# KC_BaseBoard4CompareTest-V0_21.net
KiCad netlist of a schematic drawn in Altium Designer
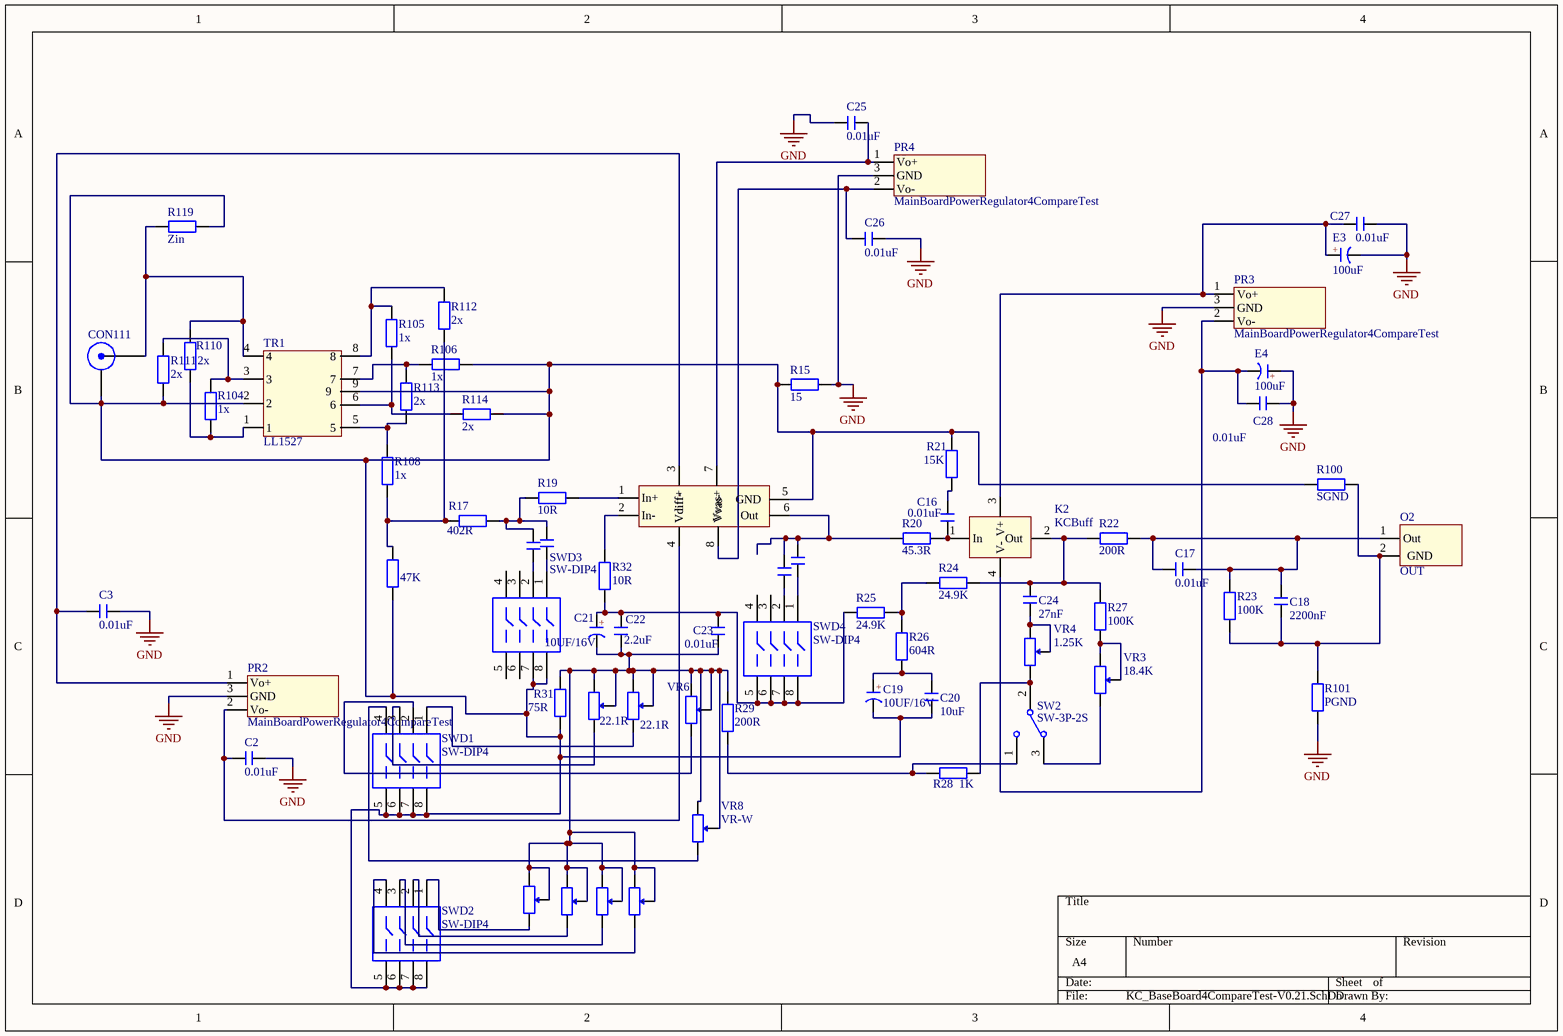
[diagram p0: KC_BaseBoard4CompareTest-V0.21.SchDoc]

(export (version "E")
  (design (tool "Eeschema 10.0.6"))
  (components
    (comp (ref "C2")
      (value "0.01uF")
      (footprint "CBB 6.3*6.3*5")
      (description "CBB电容")
      (fields (field (name "版权归属") "源创客"))
      (libsource (lib "电阻-电容-电感") (part "C-CBB"))
    )
    (comp (ref "C3")
      (value "0.01uF")
      (footprint "CBB 6.3*6.3*5")
      (description "CBB电容")
      (fields (field (name "版权归属") "源创客"))
      (libsource (lib "电阻-电容-电感") (part "C-CBB"))
    )
    (comp (ref "C16")
      (value "0.01uF")
      (footprint "CBB 6.3*6.3*5")
      (description "CBB电容")
      (fields (field (name "版权归属") "源创客"))
      (libsource (lib "电阻-电容-电感") (part "C-CBB"))
    )
    (comp (ref "C17")
      (value "0.01uF")
      (footprint "CBB 6.3*6.3*5")
      (description "CBB电容")
      (fields (field (name "版权归属") "源创客"))
      (libsource (lib "电阻-电容-电感") (part "C-CBB"))
    )
    (comp (ref "C18")
      (value "2200nF")
      (footprint "CBB 6.3*6.3*5")
      (description "CBB电容")
      (fields (field (name "版权归属") "源创客"))
      (libsource (lib "电阻-电容-电感") (part "C-CBB"))
    )
    (comp (ref "C19")
      (value "10UF/16V")
      (footprint "CAP 5.0*10*12.5")
      (description "直插电解电容")
      (fields (field (name "版权归属") "源创客"))
      (libsource (lib "电阻-电容-电感") (part "C-CAP"))
    )
    (comp (ref "C20")
      (value "10uF")
      (footprint "CBB 6.3*6.3*5")
      (description "CBB电容")
      (fields (field (name "版权归属") "源创客"))
      (libsource (lib "电阻-电容-电感") (part "C-CBB"))
    )
    (comp (ref "C21")
      (value "10UF/16V")
      (footprint "CAP 5.0*10*12.5")
      (description "直插电解电容")
      (fields (field (name "版权归属") "源创客"))
      (libsource (lib "电阻-电容-电感") (part "C-CAP"))
    )
    (comp (ref "C22")
      (value "2.2uF")
      (footprint "CBB 6.3*6.3*5")
      (description "CBB电容")
      (fields (field (name "版权归属") "源创客"))
      (libsource (lib "电阻-电容-电感") (part "C-CBB"))
    )
    (comp (ref "C23")
      (value "0.01uF")
      (footprint "CBB 6.3*6.3*5")
      (description "CBB电容")
      (fields (field (name "版权归属") "源创客"))
      (libsource (lib "电阻-电容-电感") (part "C-CBB"))
    )
    (comp (ref "C24")
      (value "27nF")
      (footprint "CBB 6.3*6.3*5")
      (description "CBB电容")
      (fields (field (name "版权归属") "源创客"))
      (libsource (lib "电阻-电容-电感") (part "C-CBB"))
    )
    (comp (ref "C25")
      (value "0.01uF")
      (footprint "CBB 6.3*6.3*5")
      (description "CBB电容")
      (fields (field (name "版权归属") "源创客"))
      (libsource (lib "电阻-电容-电感") (part "C-CBB"))
    )
    (comp (ref "C26")
      (value "0.01uF")
      (footprint "CBB 6.3*6.3*5")
      (description "CBB电容")
      (fields (field (name "版权归属") "源创客"))
      (libsource (lib "电阻-电容-电感") (part "C-CBB"))
    )
    (comp (ref "C27")
      (value "0.01uF")
      (footprint "CBB 6.3*6.3*5")
      (description "CBB电容")
      (fields (field (name "版权归属") "源创客"))
      (libsource (lib "电阻-电容-电感") (part "C-CBB"))
    )
    (comp (ref "C28")
      (value "0.01uF")
      (footprint "CBB 6.3*6.3*5")
      (description "CBB电容")
      (fields (field (name "版权归属") "源创客"))
      (libsource (lib "电阻-电容-电感") (part "C-CBB"))
    )
    (comp (ref "C302")
      (value "100pF")
      (footprint "CBB 6.3*6.3*5")
      (description "CBB电容")
      (fields (field (name "版权归属") "源创客"))
      (libsource (lib "电阻-电容-电感") (part "C-CBB"))
    )
    (comp (ref "C303")
      (value "20pF")
      (footprint "CBB 6.3*6.3*5")
      (description "CBB电容")
      (fields (field (name "版权归属") "源创客"))
      (libsource (lib "电阻-电容-电感") (part "C-CBB"))
    )
    (comp (ref "C402")
      (value "100pF")
      (footprint "CBB 6.3*6.3*5")
      (description "CBB电容")
      (fields (field (name "版权归属") "源创客"))
      (libsource (lib "电阻-电容-电感") (part "C-CBB"))
    )
    (comp (ref "C403")
      (value "20pF")
      (footprint "CBB 6.3*6.3*5")
      (description "CBB电容")
      (fields (field (name "版权归属") "源创客"))
      (libsource (lib "电阻-电容-电感") (part "C-CBB"))
    )
    (comp (ref "CON111")
      (value "RCA")
      (footprint "RCA-RJ255")
      (description "RCA Connector")
      (fields (field (name "PUBLISHER") "Altium Limited"))
      (libsource (lib "Connectors") (part "RCA"))
    )
    (comp (ref "E3")
      (value "100uF")
      (footprint "CAP 5.0*6.5*12.5")
      (description "直插电解电容")
      (fields (field (name "版权归属") "源创客"))
      (libsource (lib "") (part "C-CAP_1"))
    )
    (comp (ref "E4")
      (value "100uF")
      (footprint "CAP 5.0*6.5*12.5")
      (description "直插电解电容")
      (fields (field (name "版权归属") "源创客"))
      (libsource (lib "") (part "C-CAP_1"))
    )
    (comp (ref "K2")
      (value "KCBuff")
      (footprint "KCBuff_M4")
      (description "King Cello Buffer Stage")
      (libsource (lib "KC_amp") (part "KCBuff"))
    )
    (comp (ref "KC2")
      (value "KCInputVas_V0.2")
      (footprint "KCIn_VAS_M4_V0.2")
      (description "King Cello Input Stage and VAS")
      (libsource (lib "KC_amp") (part "KCInputVas_V0.2"))
    )
    (comp (ref "O2")
      (value "OUT")
      (footprint "Signal_Terminal")
      (description "Signal Out")
      (libsource (lib "KC_amp") (part "Signal_Out"))
    )
    (comp (ref "PR2")
      (value "MainBoardPowerRegulator4CompareTest")
      (footprint "KC_MBPowerReg4Compare")
      (description "King Cello Compare Test Power")
      (libsource (lib "KC_amp") (part "MainBoardPowerRegulator4CompareTest"))
    )
    (comp (ref "PR3")
      (value "MainBoardPowerRegulator4CompareTest")
      (footprint "KC_MBPowerReg4Compare")
      (description "King Cello Compare Test Power")
      (libsource (lib "KC_amp") (part "MainBoardPowerRegulator4CompareTest"))
    )
    (comp (ref "PR4")
      (value "MainBoardPowerRegulator4CompareTest")
      (footprint "KC_MBPowerReg4Compare")
      (description "King Cello Compare Test Power")
      (libsource (lib "KC_amp") (part "MainBoardPowerRegulator4CompareTest"))
    )
    (comp (ref "R15")
      (value "15")
      (footprint "RS 1/4W")
      (description "直插色环电阻")
      (fields (field (name "版权归属") "源创客"))
      (libsource (lib "电阻-电容-电感") (part "R-CRR"))
    )
    (comp (ref "R17")
      (value "402R")
      (footprint "RS 1/4W")
      (description "直插色环电阻")
      (fields (field (name "版权归属") "源创客"))
      (libsource (lib "电阻-电容-电感") (part "R-CRR"))
    )
    (comp (ref "R19")
      (value "10R")
      (footprint "RS 1/4W")
      (description "直插色环电阻")
      (fields (field (name "版权归属") "源创客"))
      (libsource (lib "电阻-电容-电感") (part "R-CRR"))
    )
    (comp (ref "R20")
      (value "45.3R")
      (footprint "RS 1/4W")
      (description "直插色环电阻")
      (fields (field (name "版权归属") "源创客"))
      (libsource (lib "电阻-电容-电感") (part "R-CRR"))
    )
    (comp (ref "R21")
      (value "15K")
      (footprint "RS 1/4W")
      (description "直插色环电阻")
      (fields (field (name "版权归属") "源创客"))
      (libsource (lib "电阻-电容-电感") (part "R-CRR"))
    )
    (comp (ref "R22")
      (value "200R")
      (footprint "RS 1/4W")
      (description "直插色环电阻")
      (fields (field (name "版权归属") "源创客"))
      (libsource (lib "电阻-电容-电感") (part "R-CRR"))
    )
    (comp (ref "R23")
      (value "100K")
      (footprint "RS 1/4W")
      (description "直插色环电阻")
      (fields (field (name "版权归属") "源创客"))
      (libsource (lib "电阻-电容-电感") (part "R-CRR"))
    )
    (comp (ref "R24")
      (value "24.9K")
      (footprint "RS 1/4W")
      (description "直插色环电阻")
      (fields (field (name "版权归属") "源创客"))
      (libsource (lib "电阻-电容-电感") (part "R-CRR"))
    )
    (comp (ref "R25")
      (value "24.9K")
      (footprint "RS 1/4W")
      (description "直插色环电阻")
      (fields (field (name "版权归属") "源创客"))
      (libsource (lib "电阻-电容-电感") (part "R-CRR"))
    )
    (comp (ref "R26")
      (value "604R")
      (footprint "RS 1/4W")
      (description "直插色环电阻")
      (fields (field (name "版权归属") "源创客"))
      (libsource (lib "电阻-电容-电感") (part "R-CRR"))
    )
    (comp (ref "R27")
      (value "100K")
      (footprint "RS 1/4W")
      (description "直插色环电阻")
      (fields (field (name "版权归属") "源创客"))
      (libsource (lib "电阻-电容-电感") (part "R-CRR"))
    )
    (comp (ref "R28")
      (value "1K")
      (footprint "RS 1/4W")
      (description "直插色环电阻")
      (fields (field (name "版权归属") "源创客"))
      (libsource (lib "电阻-电容-电感") (part "R-CRR"))
    )
    (comp (ref "R29")
      (value "200R")
      (footprint "RS 1/4W")
      (description "直插色环电阻")
      (fields (field (name "版权归属") "源创客"))
      (libsource (lib "电阻-电容-电感") (part "R-CRR"))
    )
    (comp (ref "R31")
      (value "75R")
      (footprint "RS 1/4W")
      (description "直插色环电阻")
      (fields (field (name "版权归属") "源创客"))
      (libsource (lib "电阻-电容-电感") (part "R-CRR"))
    )
    (comp (ref "R32")
      (value "10R")
      (footprint "RS 1/4W")
      (description "直插色环电阻")
      (fields (field (name "版权归属") "源创客"))
      (libsource (lib "电阻-电容-电感") (part "R-CRR"))
    )
    (comp (ref "R100")
      (value "SGND")
      (footprint "RS 1/4W")
      (description "直插色环电阻")
      (fields (field (name "版权归属") "源创客"))
      (libsource (lib "电阻-电容-电感") (part "R-CRR"))
    )
    (comp (ref "R101")
      (value "PGND")
      (footprint "RS 1/4W")
      (description "直插色环电阻")
      (fields (field (name "版权归属") "源创客"))
      (libsource (lib "电阻-电容-电感") (part "R-CRR"))
    )
    (comp (ref "R104")
      (value "1x")
      (footprint "RS 1/4W")
      (description "直插色环电阻")
      (fields (field (name "版权归属") "源创客"))
      (libsource (lib "电阻-电容-电感") (part "R-CRR"))
    )
    (comp (ref "R105")
      (value "1x")
      (footprint "RS 1/4W")
      (description "直插色环电阻")
      (fields (field (name "版权归属") "源创客"))
      (libsource (lib "电阻-电容-电感") (part "R-CRR"))
    )
    (comp (ref "R106")
      (value "1x")
      (footprint "RS 1/4W")
      (description "直插色环电阻")
      (fields (field (name "版权归属") "源创客"))
      (libsource (lib "电阻-电容-电感") (part "R-CRR"))
    )
    (comp (ref "R108")
      (value "1x")
      (footprint "RS 1/4W")
      (description "直插色环电阻")
      (fields (field (name "版权归属") "源创客"))
      (libsource (lib "电阻-电容-电感") (part "R-CRR"))
    )
    (comp (ref "R110")
      (value "2x")
      (footprint "RS 1/4W")
      (description "直插色环电阻")
      (fields (field (name "版权归属") "源创客"))
      (libsource (lib "电阻-电容-电感") (part "R-CRR"))
    )
    (comp (ref "R111")
      (value "2x")
      (footprint "RS 1/4W")
      (description "直插色环电阻")
      (fields (field (name "版权归属") "源创客"))
      (libsource (lib "电阻-电容-电感") (part "R-CRR"))
    )
    (comp (ref "R112")
      (value "2x")
      (footprint "RS 1/4W")
      (description "直插色环电阻")
      (fields (field (name "版权归属") "源创客"))
      (libsource (lib "电阻-电容-电感") (part "R-CRR"))
    )
    (comp (ref "R113")
      (value "2x")
      (footprint "RS 1/4W")
      (description "直插色环电阻")
      (fields (field (name "版权归属") "源创客"))
      (libsource (lib "电阻-电容-电感") (part "R-CRR"))
    )
    (comp (ref "R114")
      (value "2x")
      (footprint "RS 1/4W")
      (description "直插色环电阻")
      (fields (field (name "版权归属") "源创客"))
      (libsource (lib "电阻-电容-电感") (part "R-CRR"))
    )
    (comp (ref "R119")
      (value "Zin")
      (footprint "RS 1/4W")
      (description "直插色环电阻")
      (fields (field (name "版权归属") "源创客"))
      (libsource (lib "电阻-电容-电感") (part "R-CRR"))
    )
    (comp (ref "R183")
      (value "47K")
      (footprint "RS 1/4W")
      (description "直插色环电阻")
      (fields (field (name "版权归属") "源创客"))
      (libsource (lib "电阻-电容-电感") (part "R-CRR"))
    )
    (comp (ref "SW2")
      (value "SW-3P-2S")
      (footprint "SS-12D06")
      (description "3 Pin 2 Switch")
      (libsource (lib "Connectors") (part "SW-3P-2S"))
    )
    (comp (ref "SWD1")
      (value "SW-DIP4")
      (footprint "DIP-8")
      (description "DIP Switch")
      (fields (field (name "PUBLISHER") "Altium Limited"))
      (libsource (lib "Miscellaneous Devices") (part "SW-DIP4"))
    )
    (comp (ref "SWD2")
      (value "SW-DIP4")
      (footprint "DIP-8")
      (description "DIP Switch")
      (fields (field (name "PUBLISHER") "Altium Limited"))
      (libsource (lib "Miscellaneous Devices") (part "SW-DIP4"))
    )
    (comp (ref "SWD3")
      (value "SW-DIP4")
      (footprint "DIP-8")
      (description "DIP Switch")
      (fields (field (name "PUBLISHER") "Altium Limited"))
      (libsource (lib "Miscellaneous Devices") (part "SW-DIP4"))
    )
    (comp (ref "SWD4")
      (value "SW-DIP4")
      (footprint "DIP-8")
      (description "DIP Switch")
      (fields (field (name "PUBLISHER") "Altium Limited"))
      (libsource (lib "Miscellaneous Devices") (part "SW-DIP4"))
    )
    (comp (ref "TR1")
      (value "LL1527")
      (footprint "LL1527")
      (description "Lundahl LL1527")
      (libsource (lib "KC_amp") (part "LL1527"))
    )
    (comp (ref "VR3")
      (value "18.4K")
      (footprint "RS 1/2W-VR")
      (description "直插可调电阻-顶调")
      (libsource (lib "电阻-电容-电感") (part "VR-W"))
    )
    (comp (ref "VR4")
      (value "1.25K")
      (footprint "RS 1/2W-VR")
      (description "直插可调电阻-顶调")
      (libsource (lib "电阻-电容-电感") (part "VR-W"))
    )
    (comp (ref "VR5")
      (value "22.1R")
      (footprint "RS 1/2W-VR")
      (description "直插可调电阻-顶调")
      (libsource (lib "电阻-电容-电感") (part "VR-W"))
    )
    (comp (ref "VR6")
      (value "22.1R")
      (footprint "RS 1/2W-VR")
      (description "直插可调电阻-顶调")
      (libsource (lib "电阻-电容-电感") (part "VR-W"))
    )
    (comp (ref "VR7")
      (value "VR-W")
      (footprint "RS 1/2W-VR")
      (description "直插可调电阻-顶调")
      (libsource (lib "电阻-电容-电感") (part "VR-W"))
    )
    (comp (ref "VR8")
      (value "VR-W")
      (footprint "RS 1/2W-VR")
      (description "直插可调电阻-顶调")
      (libsource (lib "电阻-电容-电感") (part "VR-W"))
    )
    (comp (ref "VR9")
      (value "VR-W")
      (footprint "RS 1/2W-VR")
      (description "直插可调电阻-顶调")
      (libsource (lib "电阻-电容-电感") (part "VR-W"))
    )
    (comp (ref "VR10")
      (value "VR-W")
      (footprint "RS 1/2W-VR")
      (description "直插可调电阻-顶调")
      (libsource (lib "电阻-电容-电感") (part "VR-W"))
    )
    (comp (ref "VR11")
      (value "VR-W")
      (footprint "RS 1/2W-VR")
      (description "直插可调电阻-顶调")
      (libsource (lib "电阻-电容-电感") (part "VR-W"))
    )
    (comp (ref "VR12")
      (value "VR-W")
      (footprint "RS 1/2W-VR")
      (description "直插可调电阻-顶调")
      (libsource (lib "电阻-电容-电感") (part "VR-W"))
    )
  )
  (nets
    (net (code "1") (name "GND") (class "Default")
      (node (ref "C2") (pin "2") (pinfunction "2_2") (pintype "passive"))
      (node (ref "C25") (pin "1") (pinfunction "1_1") (pintype "passive"))
      (node (ref "C26") (pin "2") (pinfunction "2_2") (pintype "passive"))
      (node (ref "C27") (pin "2") (pinfunction "2_2") (pintype "passive"))
      (node (ref "C28") (pin "2") (pinfunction "2_2") (pintype "passive"))
      (node (ref "C3") (pin "2") (pinfunction "2_2") (pintype "passive"))
      (node (ref "E3") (pin "2") (pinfunction "K_2") (pintype "passive"))
      (node (ref "E4") (pin "1") (pinfunction "A_1") (pintype "passive"))
      (node (ref "PR2") (pin "3") (pinfunction "GND_3") (pintype "passive"))
      (node (ref "PR3") (pin "3") (pinfunction "GND_3") (pintype "passive"))
      (node (ref "PR4") (pin "3") (pinfunction "GND_3") (pintype "passive"))
      (node (ref "R101") (pin "1") (pinfunction "1_1") (pintype "passive"))
      (node (ref "R15") (pin "2") (pinfunction "2_2") (pintype "passive"))
    )
    (net (code "2") (name "Net-(C16-Pad2)") (class "Default")
      (node (ref "C16") (pin "2") (pinfunction "2_2") (pintype "passive"))
      (node (ref "R21") (pin "1") (pinfunction "1_1") (pintype "passive"))
    )
    (net (code "3") (name "Net-(C19-A)") (class "Default")
      (node (ref "C19") (pin "1") (pinfunction "A_1") (pintype "passive"))
      (node (ref "C20") (pin "1") (pinfunction "1_1") (pintype "passive"))
      (node (ref "R26") (pin "1") (pinfunction "1_1") (pintype "passive"))
    )
    (net (code "4") (name "Net-(C19-K)") (class "Default")
      (node (ref "C19") (pin "2") (pinfunction "K_2") (pintype "passive"))
      (node (ref "C20") (pin "2") (pinfunction "2_2") (pintype "passive"))
      (node (ref "CON111") (pin "2") (pinfunction "Y_2") (pintype "passive"))
      (node (ref "KC2") (pin "5") (pinfunction "GND_5") (pintype "passive"))
      (node (ref "R100") (pin "1") (pinfunction "1_1") (pintype "passive"))
      (node (ref "R106") (pin "2") (pinfunction "2_2") (pintype "passive"))
      (node (ref "R111") (pin "1") (pinfunction "1_1") (pintype "passive"))
      (node (ref "R114") (pin "2") (pinfunction "2_2") (pintype "passive"))
      (node (ref "R119") (pin "2") (pinfunction "2_2") (pintype "passive"))
      (node (ref "R15") (pin "1") (pinfunction "1_1") (pintype "passive"))
      (node (ref "R183") (pin "1") (pinfunction "1_1") (pintype "passive"))
      (node (ref "R21") (pin "2") (pinfunction "2_2") (pintype "passive"))
      (node (ref "R31") (pin "1") (pinfunction "1_1") (pintype "passive"))
      (node (ref "SWD1") (pin "5") (pinfunction "5_5") (pintype "passive"))
      (node (ref "SWD1") (pin "6") (pinfunction "6_6") (pintype "passive"))
      (node (ref "SWD1") (pin "7") (pinfunction "7_7") (pintype "passive"))
      (node (ref "SWD1") (pin "8") (pinfunction "8_8") (pintype "passive"))
      (node (ref "SWD2") (pin "5") (pinfunction "5_5") (pintype "passive"))
      (node (ref "SWD2") (pin "6") (pinfunction "6_6") (pintype "passive"))
      (node (ref "SWD2") (pin "7") (pinfunction "7_7") (pintype "passive"))
      (node (ref "SWD2") (pin "8") (pinfunction "8_8") (pintype "passive"))
      (node (ref "SWD3") (pin "7") (pinfunction "7_7") (pintype "passive"))
      (node (ref "SWD3") (pin "8") (pinfunction "8_8") (pintype "passive"))
      (node (ref "TR1") (pin "2") (pinfunction "2_2") (pintype "passive"))
      (node (ref "TR1") (pin "9") (pinfunction "9_9") (pintype "passive"))
    )
    (net (code "5") (name "Net-(C21-A)") (class "Default")
      (node (ref "C21") (pin "1") (pinfunction "A_1") (pintype "passive"))
      (node (ref "C22") (pin "1") (pinfunction "1_1") (pintype "passive"))
      (node (ref "C23") (pin "1") (pinfunction "1_1") (pintype "passive"))
      (node (ref "R25") (pin "1") (pinfunction "1_1") (pintype "passive"))
      (node (ref "R32") (pin "1") (pinfunction "1_1") (pintype "passive"))
      (node (ref "SWD4") (pin "5") (pinfunction "5_5") (pintype "passive"))
      (node (ref "SWD4") (pin "6") (pinfunction "6_6") (pintype "passive"))
      (node (ref "SWD4") (pin "7") (pinfunction "7_7") (pintype "passive"))
      (node (ref "SWD4") (pin "8") (pinfunction "8_8") (pintype "passive"))
    )
    (net (code "6") (name "Net-(C21-K)") (class "Default")
      (node (ref "C21") (pin "2") (pinfunction "K_2") (pintype "passive"))
      (node (ref "C22") (pin "2") (pinfunction "2_2") (pintype "passive"))
      (node (ref "C23") (pin "2") (pinfunction "2_2") (pintype "passive"))
      (node (ref "R29") (pin "2") (pinfunction "2_2") (pintype "passive"))
      (node (ref "R31") (pin "2") (pinfunction "2_2") (pintype "passive"))
      (node (ref "VR10") (pin "1") (pinfunction "1_1") (pintype "passive"))
      (node (ref "VR10") (pin "3") (pinfunction "3_3") (pintype "passive"))
      (node (ref "VR11") (pin "1") (pinfunction "1_1") (pintype "passive"))
      (node (ref "VR11") (pin "3") (pinfunction "3_3") (pintype "passive"))
      (node (ref "VR12") (pin "1") (pinfunction "1_1") (pintype "passive"))
      (node (ref "VR12") (pin "3") (pinfunction "3_3") (pintype "passive"))
      (node (ref "VR5") (pin "1") (pinfunction "1_1") (pintype "passive"))
      (node (ref "VR5") (pin "3") (pinfunction "3_3") (pintype "passive"))
      (node (ref "VR6") (pin "1") (pinfunction "1_1") (pintype "passive"))
      (node (ref "VR6") (pin "3") (pinfunction "3_3") (pintype "passive"))
      (node (ref "VR7") (pin "1") (pinfunction "1_1") (pintype "passive"))
      (node (ref "VR7") (pin "3") (pinfunction "3_3") (pintype "passive"))
      (node (ref "VR8") (pin "1") (pinfunction "1_1") (pintype "passive"))
      (node (ref "VR8") (pin "3") (pinfunction "3_3") (pintype "passive"))
      (node (ref "VR9") (pin "1") (pinfunction "1_1") (pintype "passive"))
      (node (ref "VR9") (pin "3") (pinfunction "3_3") (pintype "passive"))
    )
    (net (code "7") (name "Net-(C24-Pad2)") (class "Default")
      (node (ref "C24") (pin "2") (pinfunction "2_2") (pintype "passive"))
      (node (ref "VR4") (pin "1") (pinfunction "1_1") (pintype "passive"))
      (node (ref "VR4") (pin "3") (pinfunction "3_3") (pintype "passive"))
    )
    (net (code "8") (name "Net-(C302-Pad1)") (class "Default")
      (node (ref "C302") (pin "1") (pinfunction "1_1") (pintype "passive"))
      (node (ref "SWD3") (pin "2") (pinfunction "2_2") (pintype "passive"))
    )
    (net (code "9") (name "Net-(C302-Pad2)") (class "Default")
      (node (ref "C302") (pin "2") (pinfunction "2_2") (pintype "passive"))
      (node (ref "C303") (pin "2") (pinfunction "2_2") (pintype "passive"))
      (node (ref "R17") (pin "2") (pinfunction "2_2") (pintype "passive"))
      (node (ref "R19") (pin "1") (pinfunction "1_1") (pintype "passive"))
    )
    (net (code "10") (name "Net-(C303-Pad1)") (class "Default")
      (node (ref "C303") (pin "1") (pinfunction "1_1") (pintype "passive"))
      (node (ref "SWD3") (pin "1") (pinfunction "1_1") (pintype "passive"))
    )
    (net (code "11") (name "Net-(C402-Pad1)") (class "Default")
      (node (ref "C402") (pin "1") (pinfunction "1_1") (pintype "passive"))
      (node (ref "SWD4") (pin "2") (pinfunction "2_2") (pintype "passive"))
    )
    (net (code "12") (name "Net-(C403-Pad1)") (class "Default")
      (node (ref "C403") (pin "1") (pinfunction "1_1") (pintype "passive"))
      (node (ref "SWD4") (pin "1") (pinfunction "1_1") (pintype "passive"))
    )
    (net (code "13") (name "Net-(CON111-X)") (class "Default")
      (node (ref "CON111") (pin "1") (pinfunction "X_1") (pintype "passive"))
      (node (ref "R110") (pin "2") (pinfunction "2_2") (pintype "passive"))
      (node (ref "R119") (pin "1") (pinfunction "1_1") (pintype "passive"))
      (node (ref "TR1") (pin "4") (pinfunction "4_4") (pintype "passive"))
    )
    (net (code "14") (name "Net-(E3-A)") (class "Default")
      (node (ref "C27") (pin "1") (pinfunction "1_1") (pintype "passive"))
      (node (ref "E3") (pin "1") (pinfunction "A_1") (pintype "passive"))
      (node (ref "K2") (pin "3") (pinfunction "V+_3") (pintype "passive"))
      (node (ref "PR3") (pin "1") (pinfunction "Vo+_1") (pintype "passive"))
    )
    (net (code "15") (name "Net-(E4-K)") (class "Default")
      (node (ref "C28") (pin "1") (pinfunction "1_1") (pintype "passive"))
      (node (ref "E4") (pin "2") (pinfunction "K_2") (pintype "passive"))
      (node (ref "K2") (pin "4") (pinfunction "V-_4") (pintype "passive"))
      (node (ref "PR3") (pin "2") (pinfunction "Vo-_2") (pintype "passive"))
    )
    (net (code "16") (name "Net-(K2-In)") (class "Default")
      (node (ref "C16") (pin "1") (pinfunction "1_1") (pintype "passive"))
      (node (ref "K2") (pin "1") (pinfunction "In_1") (pintype "passive"))
      (node (ref "R20") (pin "2") (pinfunction "2_2") (pintype "passive"))
    )
    (net (code "17") (name "Net-(K2-Out)") (class "Default")
      (node (ref "C24") (pin "1") (pinfunction "1_1") (pintype "passive"))
      (node (ref "K2") (pin "2") (pinfunction "Out_2") (pintype "passive"))
      (node (ref "R22") (pin "2") (pinfunction "2_2") (pintype "passive"))
      (node (ref "R24") (pin "2") (pinfunction "2_2") (pintype "passive"))
      (node (ref "R27") (pin "1") (pinfunction "1_1") (pintype "passive"))
    )
    (net (code "18") (name "Net-(KC2-In+)") (class "Default")
      (node (ref "KC2") (pin "1") (pinfunction "In+_1") (pintype "passive"))
      (node (ref "R19") (pin "2") (pinfunction "2_2") (pintype "passive"))
    )
    (net (code "19") (name "Net-(KC2-In-)") (class "Default")
      (node (ref "KC2") (pin "2") (pinfunction "In-_2") (pintype "passive"))
      (node (ref "R32") (pin "2") (pinfunction "2_2") (pintype "passive"))
    )
    (net (code "20") (name "Net-(KC2-Out)") (class "Default")
      (node (ref "C402") (pin "2") (pinfunction "2_2") (pintype "passive"))
      (node (ref "C403") (pin "2") (pinfunction "2_2") (pintype "passive"))
      (node (ref "KC2") (pin "6") (pinfunction "Out_6") (pintype "passive"))
      (node (ref "R20") (pin "1") (pinfunction "1_1") (pintype "passive"))
    )
    (net (code "21") (name "Net-(KC2-Vdiff+)") (class "Default")
      (node (ref "C3") (pin "1") (pinfunction "1_1") (pintype "passive"))
      (node (ref "KC2") (pin "3") (pinfunction "Vdiff+_3") (pintype "passive"))
      (node (ref "PR2") (pin "1") (pinfunction "Vo+_1") (pintype "passive"))
    )
    (net (code "22") (name "Net-(KC2-Vdiff-)") (class "Default")
      (node (ref "C2") (pin "1") (pinfunction "1_1") (pintype "passive"))
      (node (ref "KC2") (pin "4") (pinfunction "Vdiff-_4") (pintype "passive"))
      (node (ref "PR2") (pin "2") (pinfunction "Vo-_2") (pintype "passive"))
    )
    (net (code "23") (name "Net-(KC2-Vvas+)") (class "Default")
      (node (ref "C25") (pin "2") (pinfunction "2_2") (pintype "passive"))
      (node (ref "KC2") (pin "7") (pinfunction "Vvas+_7") (pintype "passive"))
      (node (ref "PR4") (pin "1") (pinfunction "Vo+_1") (pintype "passive"))
    )
    (net (code "24") (name "Net-(KC2-Vvas-)") (class "Default")
      (node (ref "C26") (pin "1") (pinfunction "1_1") (pintype "passive"))
      (node (ref "KC2") (pin "8") (pinfunction "Vvas-_8") (pintype "passive"))
      (node (ref "PR4") (pin "2") (pinfunction "Vo-_2") (pintype "passive"))
    )
    (net (code "25") (name "Net-(O2-GND)") (class "Default")
      (node (ref "C18") (pin "2") (pinfunction "2_2") (pintype "passive"))
      (node (ref "O2") (pin "2") (pinfunction "GND_2") (pintype "passive"))
      (node (ref "R100") (pin "2") (pinfunction "2_2") (pintype "passive"))
      (node (ref "R101") (pin "2") (pinfunction "2_2") (pintype "passive"))
      (node (ref "R23") (pin "2") (pinfunction "2_2") (pintype "passive"))
    )
    (net (code "26") (name "Net-(O2-Out)") (class "Default")
      (node (ref "C17") (pin "1") (pinfunction "1_1") (pintype "passive"))
      (node (ref "C17") (pin "2") (pinfunction "2_2") (pintype "passive"))
      (node (ref "C18") (pin "1") (pinfunction "1_1") (pintype "passive"))
      (node (ref "O2") (pin "1") (pinfunction "Out_1") (pintype "passive"))
      (node (ref "R22") (pin "1") (pinfunction "1_1") (pintype "passive"))
      (node (ref "R23") (pin "1") (pinfunction "1_1") (pintype "passive"))
    )
    (net (code "27") (name "Net-(R24-Pad1)") (class "Default")
      (node (ref "R24") (pin "1") (pinfunction "1_1") (pintype "passive"))
      (node (ref "R25") (pin "2") (pinfunction "2_2") (pintype "passive"))
      (node (ref "R26") (pin "2") (pinfunction "2_2") (pintype "passive"))
    )
    (net (code "28") (name "Net-(R27-Pad2)") (class "Default")
      (node (ref "R27") (pin "2") (pinfunction "2_2") (pintype "passive"))
      (node (ref "VR3") (pin "1") (pinfunction "1_1") (pintype "passive"))
      (node (ref "VR3") (pin "3") (pinfunction "3_3") (pintype "passive"))
    )
    (net (code "29") (name "Net-(R28-Pad1)") (class "Default")
      (node (ref "R28") (pin "1") (pinfunction "1_1") (pintype "passive"))
      (node (ref "R29") (pin "1") (pinfunction "1_1") (pintype "passive"))
      (node (ref "SW2") (pin "1") (pinfunction "1_1") (pintype "passive"))
    )
    (net (code "30") (name "Net-(R28-Pad2)") (class "Default")
      (node (ref "R28") (pin "2") (pinfunction "2_2") (pintype "passive"))
      (node (ref "SW2") (pin "2") (pinfunction "2_2") (pintype "passive"))
      (node (ref "VR4") (pin "2") (pinfunction "2_2") (pintype "passive"))
    )
    (net (code "31") (name "Net-(R104-Pad1)") (class "Default")
      (node (ref "R104") (pin "1") (pinfunction "1_1") (pintype "passive"))
      (node (ref "R110") (pin "1") (pinfunction "1_1") (pintype "passive"))
      (node (ref "TR1") (pin "1") (pinfunction "1_1") (pintype "passive"))
    )
    (net (code "32") (name "Net-(R104-Pad2)") (class "Default")
      (node (ref "R104") (pin "2") (pinfunction "2_2") (pintype "passive"))
      (node (ref "R111") (pin "2") (pinfunction "2_2") (pintype "passive"))
      (node (ref "TR1") (pin "3") (pinfunction "3_3") (pintype "passive"))
    )
    (net (code "33") (name "Net-(R105-Pad1)") (class "Default")
      (node (ref "R105") (pin "1") (pinfunction "1_1") (pintype "passive"))
      (node (ref "R114") (pin "1") (pinfunction "1_1") (pintype "passive"))
      (node (ref "TR1") (pin "6") (pinfunction "6_6") (pintype "passive"))
    )
    (net (code "34") (name "Net-(R105-Pad2)") (class "Default")
      (node (ref "R105") (pin "2") (pinfunction "2_2") (pintype "passive"))
      (node (ref "R112") (pin "2") (pinfunction "2_2") (pintype "passive"))
      (node (ref "TR1") (pin "8") (pinfunction "8_8") (pintype "passive"))
    )
    (net (code "35") (name "Net-(R106-Pad1)") (class "Default")
      (node (ref "R106") (pin "1") (pinfunction "1_1") (pintype "passive"))
      (node (ref "R113") (pin "2") (pinfunction "2_2") (pintype "passive"))
      (node (ref "TR1") (pin "7") (pinfunction "7_7") (pintype "passive"))
    )
    (net (code "36") (name "Net-(R108-Pad1)") (class "Default")
      (node (ref "R108") (pin "1") (pinfunction "1_1") (pintype "passive"))
      (node (ref "R112") (pin "1") (pinfunction "1_1") (pintype "passive"))
      (node (ref "R17") (pin "1") (pinfunction "1_1") (pintype "passive"))
      (node (ref "R183") (pin "2") (pinfunction "2_2") (pintype "passive"))
    )
    (net (code "37") (name "Net-(R108-Pad2)") (class "Default")
      (node (ref "R108") (pin "2") (pinfunction "2_2") (pintype "passive"))
      (node (ref "R113") (pin "1") (pinfunction "1_1") (pintype "passive"))
      (node (ref "TR1") (pin "5") (pinfunction "5_5") (pintype "passive"))
    )
    (net (code "38") (name "Net-(SW2-Pad3)") (class "Default")
      (node (ref "SW2") (pin "3") (pinfunction "3_3") (pintype "passive"))
      (node (ref "VR3") (pin "2") (pinfunction "2_2") (pintype "passive"))
    )
    (net (code "39") (name "Net-(SWD1-Pad1)") (class "Default")
      (node (ref "SWD1") (pin "1") (pinfunction "1_1") (pintype "passive"))
      (node (ref "VR5") (pin "2") (pinfunction "2_2") (pintype "passive"))
    )
    (net (code "40") (name "Net-(SWD1-Pad2)") (class "Default")
      (node (ref "SWD1") (pin "2") (pinfunction "2_2") (pintype "passive"))
      (node (ref "VR6") (pin "2") (pinfunction "2_2") (pintype "passive"))
    )
    (net (code "41") (name "Net-(SWD1-Pad3)") (class "Default")
      (node (ref "SWD1") (pin "3") (pinfunction "3_3") (pintype "passive"))
      (node (ref "VR7") (pin "2") (pinfunction "2_2") (pintype "passive"))
    )
    (net (code "42") (name "Net-(SWD1-Pad4)") (class "Default")
      (node (ref "SWD1") (pin "4") (pinfunction "4_4") (pintype "passive"))
      (node (ref "VR8") (pin "2") (pinfunction "2_2") (pintype "passive"))
    )
    (net (code "43") (name "Net-(SWD2-Pad1)") (class "Default")
      (node (ref "SWD2") (pin "1") (pinfunction "1_1") (pintype "passive"))
      (node (ref "VR12") (pin "2") (pinfunction "2_2") (pintype "passive"))
    )
    (net (code "44") (name "Net-(SWD2-Pad2)") (class "Default")
      (node (ref "SWD2") (pin "2") (pinfunction "2_2") (pintype "passive"))
      (node (ref "VR11") (pin "2") (pinfunction "2_2") (pintype "passive"))
    )
    (net (code "45") (name "Net-(SWD2-Pad3)") (class "Default")
      (node (ref "SWD2") (pin "3") (pinfunction "3_3") (pintype "passive"))
      (node (ref "VR10") (pin "2") (pinfunction "2_2") (pintype "passive"))
    )
    (net (code "46") (name "Net-(SWD2-Pad4)") (class "Default")
      (node (ref "SWD2") (pin "4") (pinfunction "4_4") (pintype "passive"))
      (node (ref "VR9") (pin "2") (pinfunction "2_2") (pintype "passive"))
    )
    (net (code "47") (name "unconnected-(SWD3-Pad3)") (class "Default")
      (node (ref "SWD3") (pin "3") (pinfunction "3_3") (pintype "passive"))
    )
    (net (code "48") (name "unconnected-(SWD3-Pad4)") (class "Default")
      (node (ref "SWD3") (pin "4") (pinfunction "4_4") (pintype "passive"))
    )
    (net (code "49") (name "unconnected-(SWD3-Pad5)") (class "Default")
      (node (ref "SWD3") (pin "5") (pinfunction "5_5") (pintype "passive"))
    )
    (net (code "50") (name "unconnected-(SWD3-Pad6)") (class "Default")
      (node (ref "SWD3") (pin "6") (pinfunction "6_6") (pintype "passive"))
    )
    (net (code "51") (name "unconnected-(SWD4-Pad3)") (class "Default")
      (node (ref "SWD4") (pin "3") (pinfunction "3_3") (pintype "passive"))
    )
    (net (code "52") (name "unconnected-(SWD4-Pad4)") (class "Default")
      (node (ref "SWD4") (pin "4") (pinfunction "4_4") (pintype "passive"))
    )
  )
)
